# hd6303-mb-ram-rom-x1_3.net
KiCad netlist of a schematic drawn in EAGLE
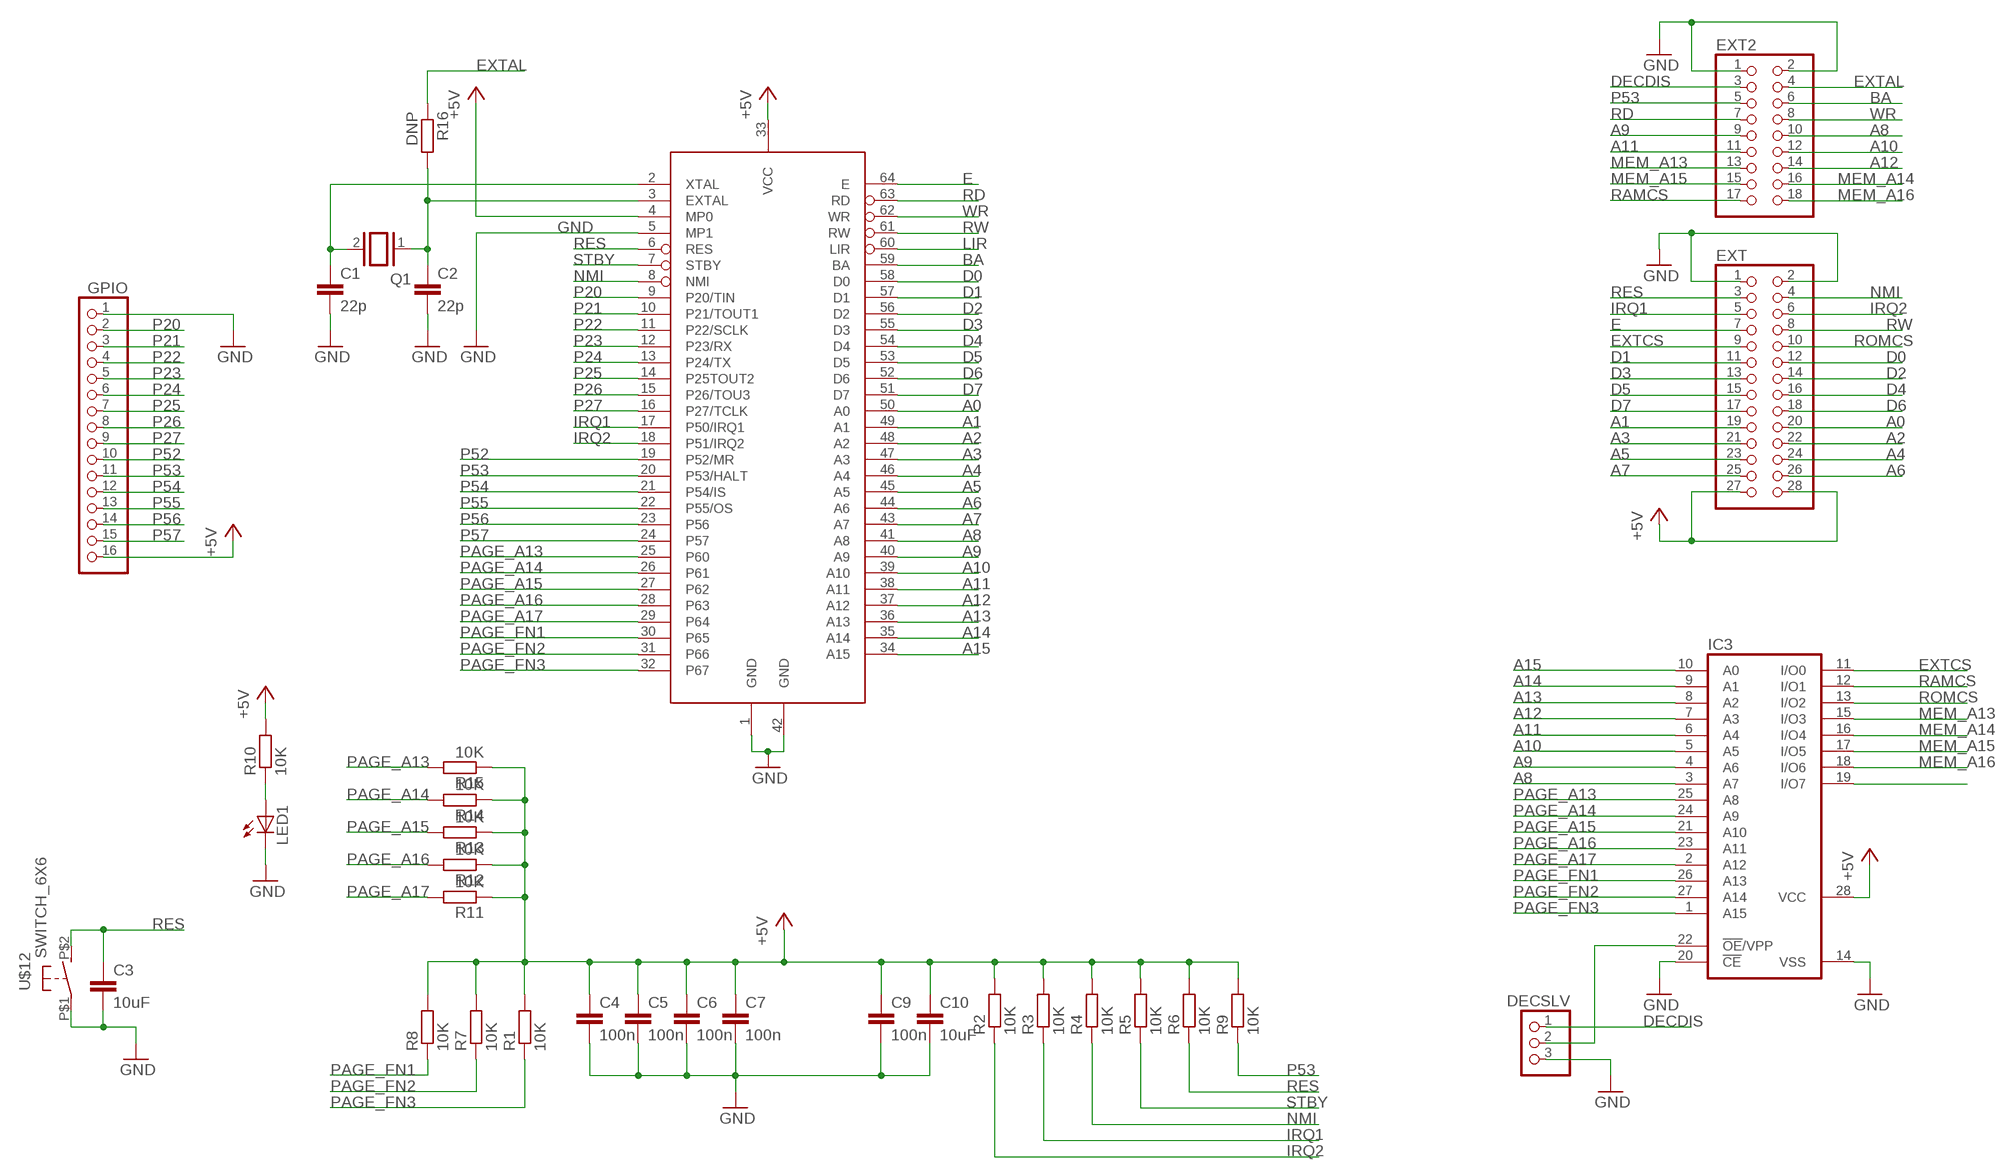
[diagram p0: schematic, sheet 1]
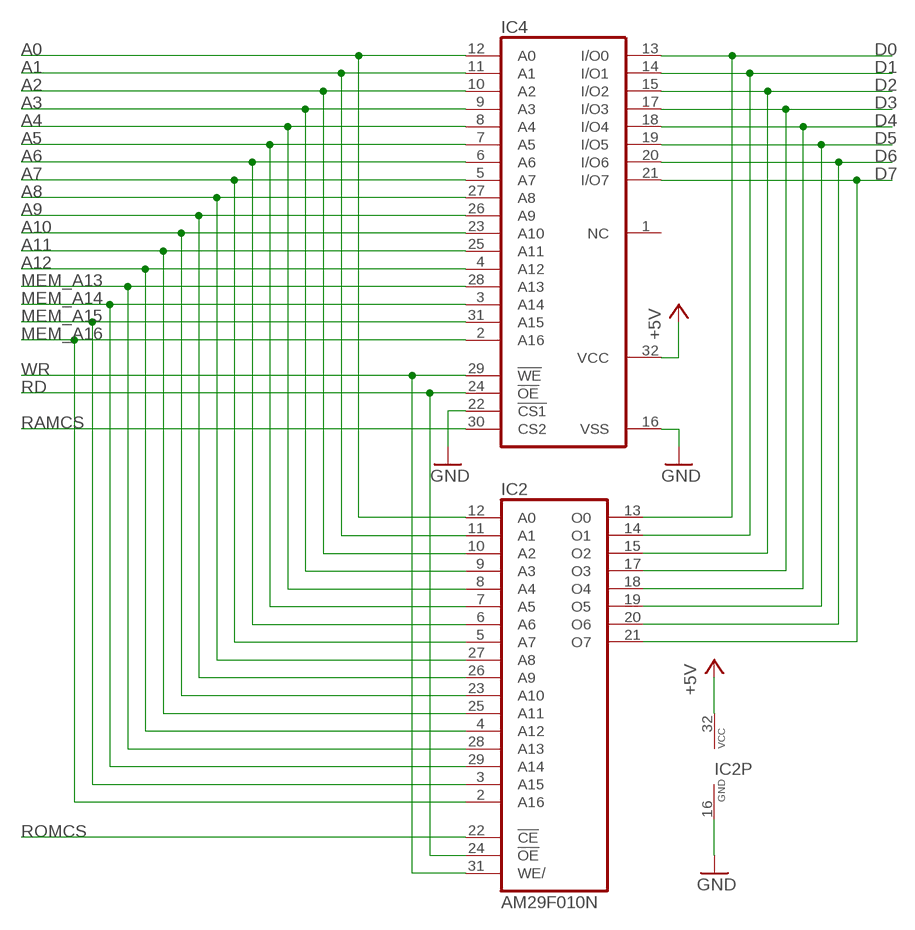
[diagram p1: schematic, sheet 2]

(export (version "E")
  (design (tool "Eeschema 10.0.6"))
  (components
    (comp (ref "C1")
      (value "22p")
      (footprint "eagle-import:C0603")
      (libsource (lib "eagle-import") (part "rcl_334_C-EUC0603"))
    )
    (comp (ref "C2")
      (value "22p")
      (footprint "eagle-import:C0603")
      (libsource (lib "eagle-import") (part "C-EUC0603"))
    )
    (comp (ref "C3")
      (value "10uF")
      (footprint "eagle-import:C0805")
      (libsource (lib "eagle-import") (part "resistor_348_C-EUC0805"))
    )
    (comp (ref "C4")
      (value "100n")
      (footprint "eagle-import:C0603")
      (libsource (lib "eagle-import") (part "C-EUC0603"))
    )
    (comp (ref "C5")
      (value "100n")
      (footprint "eagle-import:C0603")
      (libsource (lib "eagle-import") (part "C-EUC0603"))
    )
    (comp (ref "C6")
      (value "100n")
      (footprint "eagle-import:C0603")
      (libsource (lib "eagle-import") (part "C-EUC0603"))
    )
    (comp (ref "C7")
      (value "100n")
      (footprint "eagle-import:C0603")
      (libsource (lib "eagle-import") (part "C-EUC0603"))
    )
    (comp (ref "C9")
      (value "100n")
      (footprint "eagle-import:C0603")
      (libsource (lib "eagle-import") (part "C-EUC0603"))
    )
    (comp (ref "C10")
      (value "10uF")
      (footprint "eagle-import:C0805")
      (libsource (lib "eagle-import") (part "resistor_348_C-EUC0805"))
    )
    (comp (ref "DECSLV")
      (value "PINHD-1X3")
      (footprint "eagle-import:1X03")
      (libsource (lib "eagle-import") (part "PINHD-1X3"))
    )
    (comp (ref "EXT")
      (value "PINHD-2X14")
      (footprint "eagle-import:2X14")
      (libsource (lib "eagle-import") (part "PINHD-2X14"))
    )
    (comp (ref "EXT2")
      (value "PINHD-2X9")
      (footprint "eagle-import:2X09")
      (libsource (lib "eagle-import") (part "PINHD-2X9"))
    )
    (comp (ref "GPIO")
      (value "PINHD-1X16")
      (footprint "eagle-import:1X16")
      (libsource (lib "eagle-import") (part "PINHD-1X16"))
    )
    (comp (ref "IC3")
      (value "27512G")
      (footprint "eagle-import:DIL28-6")
      (libsource (lib "eagle-import") (part "27512G"))
    )
    (comp (ref "LED1")
      (value "LED5MM")
      (footprint "eagle-import:LED5MM")
      (libsource (lib "eagle-import") (part "LED5MM"))
    )
    (comp (ref "Q1")
      (value "XTAL/S")
      (footprint "eagle-import:QS")
      (libsource (lib "eagle-import") (part "XTAL/S"))
    )
    (comp (ref "R1")
      (value "10K")
      (footprint "eagle-import:R0603")
      (libsource (lib "eagle-import") (part "R-EU_R0603"))
    )
    (comp (ref "R2")
      (value "10K")
      (footprint "eagle-import:R0603")
      (libsource (lib "eagle-import") (part "R-EU_R0603"))
    )
    (comp (ref "R3")
      (value "10K")
      (footprint "eagle-import:R0603")
      (libsource (lib "eagle-import") (part "R-EU_R0603"))
    )
    (comp (ref "R4")
      (value "10K")
      (footprint "eagle-import:R0603")
      (libsource (lib "eagle-import") (part "R-EU_R0603"))
    )
    (comp (ref "R5")
      (value "10K")
      (footprint "eagle-import:R0603")
      (libsource (lib "eagle-import") (part "R-EU_R0603"))
    )
    (comp (ref "R6")
      (value "10K")
      (footprint "eagle-import:R0603")
      (libsource (lib "eagle-import") (part "R-EU_R0603"))
    )
    (comp (ref "R7")
      (value "10K")
      (footprint "eagle-import:R0603")
      (libsource (lib "eagle-import") (part "R-EU_R0603"))
    )
    (comp (ref "R8")
      (value "10K")
      (footprint "eagle-import:R0603")
      (libsource (lib "eagle-import") (part "R-EU_R0603"))
    )
    (comp (ref "R9")
      (value "10K")
      (footprint "eagle-import:R0603")
      (libsource (lib "eagle-import") (part "R-EU_R0603"))
    )
    (comp (ref "R10")
      (value "10K")
      (footprint "eagle-import:R0603")
      (libsource (lib "eagle-import") (part "R-EU_R0603"))
    )
    (comp (ref "R11")
      (value "10K")
      (footprint "eagle-import:R0603")
      (libsource (lib "eagle-import") (part "R-EU_R0603"))
    )
    (comp (ref "R12")
      (value "10K")
      (footprint "eagle-import:R0603")
      (libsource (lib "eagle-import") (part "R-EU_R0603"))
    )
    (comp (ref "R13")
      (value "10K")
      (footprint "eagle-import:R0603")
      (libsource (lib "eagle-import") (part "R-EU_R0603"))
    )
    (comp (ref "R14")
      (value "10K")
      (footprint "eagle-import:R0603")
      (libsource (lib "eagle-import") (part "R-EU_R0603"))
    )
    (comp (ref "R15")
      (value "10K")
      (footprint "eagle-import:R0603")
      (libsource (lib "eagle-import") (part "R-EU_R0603"))
    )
    (comp (ref "R16")
      (value "DNP")
      (footprint "eagle-import:R0603")
      (libsource (lib "eagle-import") (part "R-EU_R0603"))
    )
    (comp (ref "U$1")
      (value "HD6303YCP")
      (footprint "eagle-import:DP-64S")
      (libsource (lib "eagle-import") (part "HD6303YCP"))
    )
    (comp (ref "U$12")
      (value "SWITCH_6X6")
      (footprint "eagle-import:SWITCH_6X6")
      (libsource (lib "eagle-import") (part "SWITCH_6X6"))
    )
    (comp (ref "IC2")
      (value "AM29F010N")
      (footprint "eagle-import:DIP32")
      (libsource (lib "eagle-import") (part "AM29F010N"))
    )
    (comp (ref "IC4")
      (value "628128P")
      (footprint "eagle-import:DIL32")
      (libsource (lib "eagle-import") (part "628128P"))
    )
  )
  (nets
    (net (code "1") (name "+5V") (class "Default")
      (node (ref "C10") (pin "1") (pinfunction "1_1") (pintype "passive"))
      (node (ref "C4") (pin "1") (pinfunction "1_1") (pintype "passive"))
      (node (ref "C5") (pin "1") (pinfunction "1_1") (pintype "passive"))
      (node (ref "C6") (pin "1") (pinfunction "1_1") (pintype "passive"))
      (node (ref "C7") (pin "1") (pinfunction "1_1") (pintype "passive"))
      (node (ref "C9") (pin "1") (pinfunction "1_1") (pintype "passive"))
      (node (ref "EXT") (pin "27") (pinfunction "27_27") (pintype "passive"))
      (node (ref "EXT") (pin "28") (pinfunction "28_28") (pintype "passive"))
      (node (ref "GPIO") (pin "16") (pinfunction "16_16") (pintype "passive"))
      (node (ref "IC2") (pin "32") (pinfunction "VCC_32") (pintype "power_in"))
      (node (ref "IC3") (pin "28") (pinfunction "VCC_28") (pintype "power_in"))
      (node (ref "IC4") (pin "32") (pinfunction "VCC_32") (pintype "power_in"))
      (node (ref "R1") (pin "2") (pinfunction "2_2") (pintype "passive"))
      (node (ref "R10") (pin "2") (pinfunction "2_2") (pintype "passive"))
      (node (ref "R11") (pin "1") (pinfunction "1_1") (pintype "passive"))
      (node (ref "R12") (pin "1") (pinfunction "1_1") (pintype "passive"))
      (node (ref "R13") (pin "1") (pinfunction "1_1") (pintype "passive"))
      (node (ref "R14") (pin "1") (pinfunction "1_1") (pintype "passive"))
      (node (ref "R15") (pin "1") (pinfunction "1_1") (pintype "passive"))
      (node (ref "R2") (pin "2") (pinfunction "2_2") (pintype "passive"))
      (node (ref "R3") (pin "2") (pinfunction "2_2") (pintype "passive"))
      (node (ref "R4") (pin "2") (pinfunction "2_2") (pintype "passive"))
      (node (ref "R5") (pin "2") (pinfunction "2_2") (pintype "passive"))
      (node (ref "R6") (pin "2") (pinfunction "2_2") (pintype "passive"))
      (node (ref "R7") (pin "2") (pinfunction "2_2") (pintype "passive"))
      (node (ref "R8") (pin "2") (pinfunction "2_2") (pintype "passive"))
      (node (ref "R9") (pin "2") (pinfunction "2_2") (pintype "passive"))
      (node (ref "U$1") (pin "33") (pinfunction "VCC_33") (pintype "power_in"))
      (node (ref "U$1") (pin "4") (pinfunction "MP0_4") (pintype "input"))
    )
    (net (code "2") (name "A0") (class "Default")
      (node (ref "EXT") (pin "20") (pinfunction "20_20") (pintype "passive"))
      (node (ref "IC2") (pin "12") (pinfunction "A0_12") (pintype "input"))
      (node (ref "IC4") (pin "12") (pinfunction "A0_12") (pintype "input"))
      (node (ref "U$1") (pin "50") (pinfunction "A0_50") (pintype "output"))
    )
    (net (code "3") (name "A1") (class "Default")
      (node (ref "EXT") (pin "19") (pinfunction "19_19") (pintype "passive"))
      (node (ref "IC2") (pin "11") (pinfunction "A1_11") (pintype "input"))
      (node (ref "IC4") (pin "11") (pinfunction "A1_11") (pintype "input"))
      (node (ref "U$1") (pin "49") (pinfunction "A1_49") (pintype "output"))
    )
    (net (code "4") (name "A2") (class "Default")
      (node (ref "EXT") (pin "22") (pinfunction "22_22") (pintype "passive"))
      (node (ref "IC2") (pin "10") (pinfunction "A2_10") (pintype "input"))
      (node (ref "IC4") (pin "10") (pinfunction "A2_10") (pintype "input"))
      (node (ref "U$1") (pin "48") (pinfunction "A2_48") (pintype "output"))
    )
    (net (code "5") (name "A3") (class "Default")
      (node (ref "EXT") (pin "21") (pinfunction "21_21") (pintype "passive"))
      (node (ref "IC2") (pin "9") (pinfunction "A3_9") (pintype "input"))
      (node (ref "IC4") (pin "9") (pinfunction "A3_9") (pintype "input"))
      (node (ref "U$1") (pin "47") (pinfunction "A3_47") (pintype "output"))
    )
    (net (code "6") (name "A4") (class "Default")
      (node (ref "EXT") (pin "24") (pinfunction "24_24") (pintype "passive"))
      (node (ref "IC2") (pin "8") (pinfunction "A4_8") (pintype "input"))
      (node (ref "IC4") (pin "8") (pinfunction "A4_8") (pintype "input"))
      (node (ref "U$1") (pin "46") (pinfunction "A4_46") (pintype "output"))
    )
    (net (code "7") (name "A5") (class "Default")
      (node (ref "EXT") (pin "23") (pinfunction "23_23") (pintype "passive"))
      (node (ref "IC2") (pin "7") (pinfunction "A5_7") (pintype "input"))
      (node (ref "IC4") (pin "7") (pinfunction "A5_7") (pintype "input"))
      (node (ref "U$1") (pin "45") (pinfunction "A5_45") (pintype "output"))
    )
    (net (code "8") (name "A6") (class "Default")
      (node (ref "EXT") (pin "26") (pinfunction "26_26") (pintype "passive"))
      (node (ref "IC2") (pin "6") (pinfunction "A6_6") (pintype "input"))
      (node (ref "IC4") (pin "6") (pinfunction "A6_6") (pintype "input"))
      (node (ref "U$1") (pin "44") (pinfunction "A6_44") (pintype "output"))
    )
    (net (code "9") (name "A7") (class "Default")
      (node (ref "EXT") (pin "25") (pinfunction "25_25") (pintype "passive"))
      (node (ref "IC2") (pin "5") (pinfunction "A7_5") (pintype "input"))
      (node (ref "IC4") (pin "5") (pinfunction "A7_5") (pintype "input"))
      (node (ref "U$1") (pin "43") (pinfunction "A7_43") (pintype "output"))
    )
    (net (code "10") (name "A8") (class "Default")
      (node (ref "EXT2") (pin "10") (pinfunction "10_10") (pintype "passive"))
      (node (ref "IC2") (pin "27") (pinfunction "A8_27") (pintype "input"))
      (node (ref "IC3") (pin "3") (pinfunction "A7_3") (pintype "input"))
      (node (ref "IC4") (pin "27") (pinfunction "A8_27") (pintype "input"))
      (node (ref "U$1") (pin "41") (pinfunction "A8_41") (pintype "output"))
    )
    (net (code "11") (name "A9") (class "Default")
      (node (ref "EXT2") (pin "9") (pinfunction "9_9") (pintype "passive"))
      (node (ref "IC2") (pin "26") (pinfunction "A9_26") (pintype "input"))
      (node (ref "IC3") (pin "4") (pinfunction "A6_4") (pintype "input"))
      (node (ref "IC4") (pin "26") (pinfunction "A9_26") (pintype "input"))
      (node (ref "U$1") (pin "40") (pinfunction "A9_40") (pintype "output"))
    )
    (net (code "12") (name "A10") (class "Default")
      (node (ref "EXT2") (pin "12") (pinfunction "12_12") (pintype "passive"))
      (node (ref "IC2") (pin "23") (pinfunction "A10_23") (pintype "input"))
      (node (ref "IC3") (pin "5") (pinfunction "A5_5") (pintype "input"))
      (node (ref "IC4") (pin "23") (pinfunction "A10_23") (pintype "input"))
      (node (ref "U$1") (pin "39") (pinfunction "A10_39") (pintype "output"))
    )
    (net (code "13") (name "A11") (class "Default")
      (node (ref "EXT2") (pin "11") (pinfunction "11_11") (pintype "passive"))
      (node (ref "IC2") (pin "25") (pinfunction "A11_25") (pintype "input"))
      (node (ref "IC3") (pin "6") (pinfunction "A4_6") (pintype "input"))
      (node (ref "IC4") (pin "25") (pinfunction "A11_25") (pintype "input"))
      (node (ref "U$1") (pin "38") (pinfunction "A11_38") (pintype "output"))
    )
    (net (code "14") (name "A12") (class "Default")
      (node (ref "EXT2") (pin "14") (pinfunction "14_14") (pintype "passive"))
      (node (ref "IC2") (pin "4") (pinfunction "A12_4") (pintype "input"))
      (node (ref "IC3") (pin "7") (pinfunction "A3_7") (pintype "input"))
      (node (ref "IC4") (pin "4") (pinfunction "A12_4") (pintype "input"))
      (node (ref "U$1") (pin "37") (pinfunction "A12_37") (pintype "output"))
    )
    (net (code "15") (name "A13") (class "Default")
      (node (ref "IC3") (pin "8") (pinfunction "A2_8") (pintype "input"))
      (node (ref "U$1") (pin "36") (pinfunction "A13_36") (pintype "output"))
    )
    (net (code "16") (name "A14") (class "Default")
      (node (ref "IC3") (pin "9") (pinfunction "A1_9") (pintype "input"))
      (node (ref "U$1") (pin "35") (pinfunction "A14_35") (pintype "output"))
    )
    (net (code "17") (name "A15") (class "Default")
      (node (ref "IC3") (pin "10") (pinfunction "A0_10") (pintype "input"))
      (node (ref "U$1") (pin "34") (pinfunction "A15_34") (pintype "output"))
    )
    (net (code "18") (name "BA") (class "Default")
      (node (ref "EXT2") (pin "6") (pinfunction "6_6") (pintype "passive"))
      (node (ref "U$1") (pin "59") (pinfunction "BA_59") (pintype "output"))
    )
    (net (code "19") (name "D0") (class "Default")
      (node (ref "EXT") (pin "12") (pinfunction "12_12") (pintype "passive"))
      (node (ref "IC2") (pin "13") (pinfunction "O0_13") (pintype "tri_state"))
      (node (ref "IC4") (pin "13") (pinfunction "I/O0_13") (pintype "bidirectional"))
      (node (ref "U$1") (pin "58") (pinfunction "D0_58") (pintype "bidirectional"))
    )
    (net (code "20") (name "D1") (class "Default")
      (node (ref "EXT") (pin "11") (pinfunction "11_11") (pintype "passive"))
      (node (ref "IC2") (pin "14") (pinfunction "O1_14") (pintype "tri_state"))
      (node (ref "IC4") (pin "14") (pinfunction "I/O1_14") (pintype "bidirectional"))
      (node (ref "U$1") (pin "57") (pinfunction "D1_57") (pintype "bidirectional"))
    )
    (net (code "21") (name "D2") (class "Default")
      (node (ref "EXT") (pin "14") (pinfunction "14_14") (pintype "passive"))
      (node (ref "IC2") (pin "15") (pinfunction "O2_15") (pintype "tri_state"))
      (node (ref "IC4") (pin "15") (pinfunction "I/O2_15") (pintype "bidirectional"))
      (node (ref "U$1") (pin "56") (pinfunction "D2_56") (pintype "bidirectional"))
    )
    (net (code "22") (name "D3") (class "Default")
      (node (ref "EXT") (pin "13") (pinfunction "13_13") (pintype "passive"))
      (node (ref "IC2") (pin "17") (pinfunction "O3_17") (pintype "tri_state"))
      (node (ref "IC4") (pin "17") (pinfunction "I/O3_17") (pintype "bidirectional"))
      (node (ref "U$1") (pin "55") (pinfunction "D3_55") (pintype "bidirectional"))
    )
    (net (code "23") (name "D4") (class "Default")
      (node (ref "EXT") (pin "16") (pinfunction "16_16") (pintype "passive"))
      (node (ref "IC2") (pin "18") (pinfunction "O4_18") (pintype "tri_state"))
      (node (ref "IC4") (pin "18") (pinfunction "I/O4_18") (pintype "bidirectional"))
      (node (ref "U$1") (pin "54") (pinfunction "D4_54") (pintype "bidirectional"))
    )
    (net (code "24") (name "D5") (class "Default")
      (node (ref "EXT") (pin "15") (pinfunction "15_15") (pintype "passive"))
      (node (ref "IC2") (pin "19") (pinfunction "O5_19") (pintype "tri_state"))
      (node (ref "IC4") (pin "19") (pinfunction "I/O5_19") (pintype "bidirectional"))
      (node (ref "U$1") (pin "53") (pinfunction "D5_53") (pintype "bidirectional"))
    )
    (net (code "25") (name "D6") (class "Default")
      (node (ref "EXT") (pin "18") (pinfunction "18_18") (pintype "passive"))
      (node (ref "IC2") (pin "20") (pinfunction "O6_20") (pintype "tri_state"))
      (node (ref "IC4") (pin "20") (pinfunction "I/O6_20") (pintype "bidirectional"))
      (node (ref "U$1") (pin "52") (pinfunction "D6_52") (pintype "bidirectional"))
    )
    (net (code "26") (name "D7") (class "Default")
      (node (ref "EXT") (pin "17") (pinfunction "17_17") (pintype "passive"))
      (node (ref "IC2") (pin "21") (pinfunction "O7_21") (pintype "tri_state"))
      (node (ref "IC4") (pin "21") (pinfunction "I/O7_21") (pintype "bidirectional"))
      (node (ref "U$1") (pin "51") (pinfunction "D7_51") (pintype "bidirectional"))
    )
    (net (code "27") (name "DECDIS") (class "Default")
      (node (ref "DECSLV") (pin "1") (pinfunction "1_1") (pintype "passive"))
      (node (ref "EXT2") (pin "3") (pinfunction "3_3") (pintype "passive"))
    )
    (net (code "28") (name "E") (class "Default")
      (node (ref "EXT") (pin "7") (pinfunction "7_7") (pintype "passive"))
      (node (ref "U$1") (pin "64") (pinfunction "E_64") (pintype "output"))
    )
    (net (code "29") (name "EXTAL") (class "Default")
      (node (ref "EXT2") (pin "4") (pinfunction "4_4") (pintype "passive"))
      (node (ref "R16") (pin "1") (pinfunction "1_1") (pintype "passive"))
    )
    (net (code "30") (name "EXTCS") (class "Default")
      (node (ref "EXT") (pin "9") (pinfunction "9_9") (pintype "passive"))
      (node (ref "IC3") (pin "11") (pinfunction "I/O0_11") (pintype "tri_state"))
    )
    (net (code "31") (name "GND") (class "Default")
      (node (ref "C1") (pin "2") (pinfunction "2_2") (pintype "passive"))
      (node (ref "C10") (pin "2") (pinfunction "2_2") (pintype "passive"))
      (node (ref "C2") (pin "2") (pinfunction "2_2") (pintype "passive"))
      (node (ref "C3") (pin "2") (pinfunction "2_2") (pintype "passive"))
      (node (ref "C4") (pin "2") (pinfunction "2_2") (pintype "passive"))
      (node (ref "C5") (pin "2") (pinfunction "2_2") (pintype "passive"))
      (node (ref "C6") (pin "2") (pinfunction "2_2") (pintype "passive"))
      (node (ref "C7") (pin "2") (pinfunction "2_2") (pintype "passive"))
      (node (ref "C9") (pin "2") (pinfunction "2_2") (pintype "passive"))
      (node (ref "DECSLV") (pin "3") (pinfunction "3_3") (pintype "passive"))
      (node (ref "EXT") (pin "1") (pinfunction "1_1") (pintype "passive"))
      (node (ref "EXT") (pin "2") (pinfunction "2_2") (pintype "passive"))
      (node (ref "EXT2") (pin "1") (pinfunction "1_1") (pintype "passive"))
      (node (ref "EXT2") (pin "2") (pinfunction "2_2") (pintype "passive"))
      (node (ref "GPIO") (pin "1") (pinfunction "1_1") (pintype "passive"))
      (node (ref "IC2") (pin "16") (pinfunction "GND_16") (pintype "power_in"))
      (node (ref "IC3") (pin "14") (pinfunction "VSS_14") (pintype "power_in"))
      (node (ref "IC3") (pin "20") (pinfunction "~{CE}_20") (pintype "input"))
      (node (ref "IC4") (pin "16") (pinfunction "VSS_16") (pintype "power_in"))
      (node (ref "IC4") (pin "22") (pinfunction "~{CS1}_22") (pintype "input"))
      (node (ref "LED1") (pin "K") (pinfunction "C_K") (pintype "passive"))
      (node (ref "U$1") (pin "1") (pinfunction "GND_1") (pintype "power_in"))
      (node (ref "U$1") (pin "42") (pinfunction "GND_42") (pintype "power_in"))
      (node (ref "U$1") (pin "5") (pinfunction "MP1_5") (pintype "input"))
      (node (ref "U$12") (pin "P$1") (pinfunction "P_P$1") (pintype "passive"))
    )
    (net (code "32") (name "IRQ1") (class "Default")
      (node (ref "EXT") (pin "5") (pinfunction "5_5") (pintype "passive"))
      (node (ref "R3") (pin "1") (pinfunction "1_1") (pintype "passive"))
      (node (ref "U$1") (pin "17") (pinfunction "P50/IRQ1_17") (pintype "bidirectional"))
    )
    (net (code "33") (name "IRQ2") (class "Default")
      (node (ref "EXT") (pin "6") (pinfunction "6_6") (pintype "passive"))
      (node (ref "R2") (pin "1") (pinfunction "1_1") (pintype "passive"))
      (node (ref "U$1") (pin "18") (pinfunction "P51/IRQ2_18") (pintype "bidirectional"))
    )
    (net (code "34") (name "LIR") (class "Default")
      (node (ref "U$1") (pin "60") (pinfunction "LIR_60") (pintype "output"))
    )
    (net (code "35") (name "MEM_A13") (class "Default")
      (node (ref "EXT2") (pin "13") (pinfunction "13_13") (pintype "passive"))
      (node (ref "IC2") (pin "28") (pinfunction "A13_28") (pintype "input"))
      (node (ref "IC3") (pin "15") (pinfunction "I/O3_15") (pintype "tri_state"))
      (node (ref "IC4") (pin "28") (pinfunction "A13_28") (pintype "input"))
    )
    (net (code "36") (name "MEM_A14") (class "Default")
      (node (ref "EXT2") (pin "16") (pinfunction "16_16") (pintype "passive"))
      (node (ref "IC2") (pin "29") (pinfunction "A14_29") (pintype "input"))
      (node (ref "IC3") (pin "16") (pinfunction "I/O4_16") (pintype "tri_state"))
      (node (ref "IC4") (pin "3") (pinfunction "A14_3") (pintype "input"))
    )
    (net (code "37") (name "MEM_A15") (class "Default")
      (node (ref "EXT2") (pin "15") (pinfunction "15_15") (pintype "passive"))
      (node (ref "IC2") (pin "3") (pinfunction "A15_3") (pintype "input"))
      (node (ref "IC3") (pin "17") (pinfunction "I/O5_17") (pintype "tri_state"))
      (node (ref "IC4") (pin "31") (pinfunction "A15_31") (pintype "input"))
    )
    (net (code "38") (name "MEM_A16") (class "Default")
      (node (ref "EXT2") (pin "18") (pinfunction "18_18") (pintype "passive"))
      (node (ref "IC2") (pin "2") (pinfunction "A16_2") (pintype "input"))
      (node (ref "IC3") (pin "18") (pinfunction "I/O6_18") (pintype "tri_state"))
      (node (ref "IC4") (pin "2") (pinfunction "A16_2") (pintype "input"))
    )
    (net (code "39") (name "NMI") (class "Default")
      (node (ref "EXT") (pin "4") (pinfunction "4_4") (pintype "passive"))
      (node (ref "R4") (pin "1") (pinfunction "1_1") (pintype "passive"))
      (node (ref "U$1") (pin "8") (pinfunction "NMI_8") (pintype "input"))
    )
    (net (code "40") (name "Net-(IC3-~{OE}{slash}VPP)") (class "Default")
      (node (ref "DECSLV") (pin "2") (pinfunction "2_2") (pintype "passive"))
      (node (ref "IC3") (pin "22") (pinfunction "~{OE}/VPP_22") (pintype "input"))
    )
    (net (code "41") (name "Net-(LED1-PadA)") (class "Default")
      (node (ref "LED1") (pin "A") (pinfunction "A_A") (pintype "passive"))
      (node (ref "R10") (pin "1") (pinfunction "1_1") (pintype "passive"))
    )
    (net (code "42") (name "Net-(U$1-EXTAL)") (class "Default")
      (node (ref "C2") (pin "1") (pinfunction "1_1") (pintype "passive"))
      (node (ref "Q1") (pin "1") (pinfunction "1_1") (pintype "passive"))
      (node (ref "R16") (pin "2") (pinfunction "2_2") (pintype "passive"))
      (node (ref "U$1") (pin "3") (pinfunction "EXTAL_3") (pintype "input"))
    )
    (net (code "43") (name "Net-(U$1-XTAL)") (class "Default")
      (node (ref "C1") (pin "1") (pinfunction "1_1") (pintype "passive"))
      (node (ref "Q1") (pin "2") (pinfunction "2_2") (pintype "passive"))
      (node (ref "U$1") (pin "2") (pinfunction "XTAL_2") (pintype "input"))
    )
    (net (code "44") (name "P20") (class "Default")
      (node (ref "GPIO") (pin "2") (pinfunction "2_2") (pintype "passive"))
      (node (ref "U$1") (pin "9") (pinfunction "P20/TIN_9") (pintype "bidirectional"))
    )
    (net (code "45") (name "P21") (class "Default")
      (node (ref "GPIO") (pin "3") (pinfunction "3_3") (pintype "passive"))
      (node (ref "U$1") (pin "10") (pinfunction "P21/TOUT1_10") (pintype "bidirectional"))
    )
    (net (code "46") (name "P22") (class "Default")
      (node (ref "GPIO") (pin "4") (pinfunction "4_4") (pintype "passive"))
      (node (ref "U$1") (pin "11") (pinfunction "P22/SCLK_11") (pintype "bidirectional"))
    )
    (net (code "47") (name "P23") (class "Default")
      (node (ref "GPIO") (pin "5") (pinfunction "5_5") (pintype "passive"))
      (node (ref "U$1") (pin "12") (pinfunction "P23/RX_12") (pintype "bidirectional"))
    )
    (net (code "48") (name "P24") (class "Default")
      (node (ref "GPIO") (pin "6") (pinfunction "6_6") (pintype "passive"))
      (node (ref "U$1") (pin "13") (pinfunction "P24/TX_13") (pintype "bidirectional"))
    )
    (net (code "49") (name "P25") (class "Default")
      (node (ref "GPIO") (pin "7") (pinfunction "7_7") (pintype "passive"))
      (node (ref "U$1") (pin "14") (pinfunction "P25TOUT2_14") (pintype "bidirectional"))
    )
    (net (code "50") (name "P26") (class "Default")
      (node (ref "GPIO") (pin "8") (pinfunction "8_8") (pintype "passive"))
      (node (ref "U$1") (pin "15") (pinfunction "P26/TOU3_15") (pintype "bidirectional"))
    )
    (net (code "51") (name "P27") (class "Default")
      (node (ref "GPIO") (pin "9") (pinfunction "9_9") (pintype "passive"))
      (node (ref "U$1") (pin "16") (pinfunction "P27/TCLK_16") (pintype "bidirectional"))
    )
    (net (code "52") (name "P52") (class "Default")
      (node (ref "GPIO") (pin "10") (pinfunction "10_10") (pintype "passive"))
      (node (ref "U$1") (pin "19") (pinfunction "P52/MR_19") (pintype "bidirectional"))
    )
    (net (code "53") (name "P53") (class "Default")
      (node (ref "EXT2") (pin "5") (pinfunction "5_5") (pintype "passive"))
      (node (ref "GPIO") (pin "11") (pinfunction "11_11") (pintype "passive"))
      (node (ref "R9") (pin "1") (pinfunction "1_1") (pintype "passive"))
      (node (ref "U$1") (pin "20") (pinfunction "P53/HALT_20") (pintype "bidirectional"))
    )
    (net (code "54") (name "P54") (class "Default")
      (node (ref "GPIO") (pin "12") (pinfunction "12_12") (pintype "passive"))
      (node (ref "U$1") (pin "21") (pinfunction "P54/IS_21") (pintype "bidirectional"))
    )
    (net (code "55") (name "P55") (class "Default")
      (node (ref "GPIO") (pin "13") (pinfunction "13_13") (pintype "passive"))
      (node (ref "U$1") (pin "22") (pinfunction "P55/OS_22") (pintype "bidirectional"))
    )
    (net (code "56") (name "P56") (class "Default")
      (node (ref "GPIO") (pin "14") (pinfunction "14_14") (pintype "passive"))
      (node (ref "U$1") (pin "23") (pinfunction "P56_23") (pintype "bidirectional"))
    )
    (net (code "57") (name "P57") (class "Default")
      (node (ref "GPIO") (pin "15") (pinfunction "15_15") (pintype "passive"))
      (node (ref "U$1") (pin "24") (pinfunction "P57_24") (pintype "bidirectional"))
    )
    (net (code "58") (name "PAGE_A13") (class "Default")
      (node (ref "IC3") (pin "25") (pinfunction "A8_25") (pintype "input"))
      (node (ref "R15") (pin "2") (pinfunction "2_2") (pintype "passive"))
      (node (ref "U$1") (pin "25") (pinfunction "P60_25") (pintype "bidirectional"))
    )
    (net (code "59") (name "PAGE_A14") (class "Default")
      (node (ref "IC3") (pin "24") (pinfunction "A9_24") (pintype "input"))
      (node (ref "R14") (pin "2") (pinfunction "2_2") (pintype "passive"))
      (node (ref "U$1") (pin "26") (pinfunction "P61_26") (pintype "bidirectional"))
    )
    (net (code "60") (name "PAGE_A15") (class "Default")
      (node (ref "IC3") (pin "21") (pinfunction "A10_21") (pintype "input"))
      (node (ref "R13") (pin "2") (pinfunction "2_2") (pintype "passive"))
      (node (ref "U$1") (pin "27") (pinfunction "P62_27") (pintype "bidirectional"))
    )
    (net (code "61") (name "PAGE_A16") (class "Default")
      (node (ref "IC3") (pin "23") (pinfunction "A11_23") (pintype "input"))
      (node (ref "R12") (pin "2") (pinfunction "2_2") (pintype "passive"))
      (node (ref "U$1") (pin "28") (pinfunction "P63_28") (pintype "bidirectional"))
    )
    (net (code "62") (name "PAGE_A17") (class "Default")
      (node (ref "IC3") (pin "2") (pinfunction "A12_2") (pintype "input"))
      (node (ref "R11") (pin "2") (pinfunction "2_2") (pintype "passive"))
      (node (ref "U$1") (pin "29") (pinfunction "P64_29") (pintype "bidirectional"))
    )
    (net (code "63") (name "PAGE_FN1") (class "Default")
      (node (ref "IC3") (pin "26") (pinfunction "A13_26") (pintype "input"))
      (node (ref "R8") (pin "1") (pinfunction "1_1") (pintype "passive"))
      (node (ref "U$1") (pin "30") (pinfunction "P65_30") (pintype "bidirectional"))
    )
    (net (code "64") (name "PAGE_FN2") (class "Default")
      (node (ref "IC3") (pin "27") (pinfunction "A14_27") (pintype "input"))
      (node (ref "R7") (pin "1") (pinfunction "1_1") (pintype "passive"))
      (node (ref "U$1") (pin "31") (pinfunction "P66_31") (pintype "bidirectional"))
    )
    (net (code "65") (name "PAGE_FN3") (class "Default")
      (node (ref "IC3") (pin "1") (pinfunction "A15_1") (pintype "input"))
      (node (ref "R1") (pin "1") (pinfunction "1_1") (pintype "passive"))
      (node (ref "U$1") (pin "32") (pinfunction "P67_32") (pintype "bidirectional"))
    )
    (net (code "66") (name "RAMCS") (class "Default")
      (node (ref "EXT2") (pin "17") (pinfunction "17_17") (pintype "passive"))
      (node (ref "IC3") (pin "12") (pinfunction "I/O1_12") (pintype "tri_state"))
      (node (ref "IC4") (pin "30") (pinfunction "CS2_30") (pintype "input"))
    )
    (net (code "67") (name "RD") (class "Default")
      (node (ref "EXT2") (pin "7") (pinfunction "7_7") (pintype "passive"))
      (node (ref "IC2") (pin "24") (pinfunction "~{OE}_24") (pintype "input"))
      (node (ref "IC4") (pin "24") (pinfunction "~{OE}_24") (pintype "input"))
      (node (ref "U$1") (pin "63") (pinfunction "RD_63") (pintype "output"))
    )
    (net (code "68") (name "RES") (class "Default")
      (node (ref "C3") (pin "1") (pinfunction "1_1") (pintype "passive"))
      (node (ref "EXT") (pin "3") (pinfunction "3_3") (pintype "passive"))
      (node (ref "R6") (pin "1") (pinfunction "1_1") (pintype "passive"))
      (node (ref "U$1") (pin "6") (pinfunction "RES_6") (pintype "input"))
      (node (ref "U$12") (pin "P$2") (pinfunction "S_P$2") (pintype "passive"))
    )
    (net (code "69") (name "ROMCS") (class "Default")
      (node (ref "EXT") (pin "10") (pinfunction "10_10") (pintype "passive"))
      (node (ref "IC2") (pin "22") (pinfunction "~{CE}_22") (pintype "input"))
      (node (ref "IC3") (pin "13") (pinfunction "I/O2_13") (pintype "tri_state"))
    )
    (net (code "70") (name "RW") (class "Default")
      (node (ref "EXT") (pin "8") (pinfunction "8_8") (pintype "passive"))
      (node (ref "U$1") (pin "61") (pinfunction "RW_61") (pintype "output"))
    )
    (net (code "71") (name "STBY") (class "Default")
      (node (ref "R5") (pin "1") (pinfunction "1_1") (pintype "passive"))
      (node (ref "U$1") (pin "7") (pinfunction "STBY_7") (pintype "input"))
    )
    (net (code "72") (name "WR") (class "Default")
      (node (ref "EXT2") (pin "8") (pinfunction "8_8") (pintype "passive"))
      (node (ref "IC2") (pin "31") (pinfunction "WE/_31") (pintype "input"))
      (node (ref "IC4") (pin "29") (pinfunction "~{WE}_29") (pintype "input"))
      (node (ref "U$1") (pin "62") (pinfunction "WR_62") (pintype "output"))
    )
    (net (code "73") (name "unconnected-(IC3-I{slash}O7-Pad19)") (class "Default")
      (node (ref "IC3") (pin "19") (pinfunction "I/O7_19") (pintype "tri_state"))
    )
    (net (code "74") (name "unconnected-(IC4-NC-Pad1)") (class "Default")
      (node (ref "IC4") (pin "1") (pinfunction "NC_1") (pintype "no_connect"))
    )
  )
)
